# buck.net
KiCad netlist of a schematic drawn in EAGLE
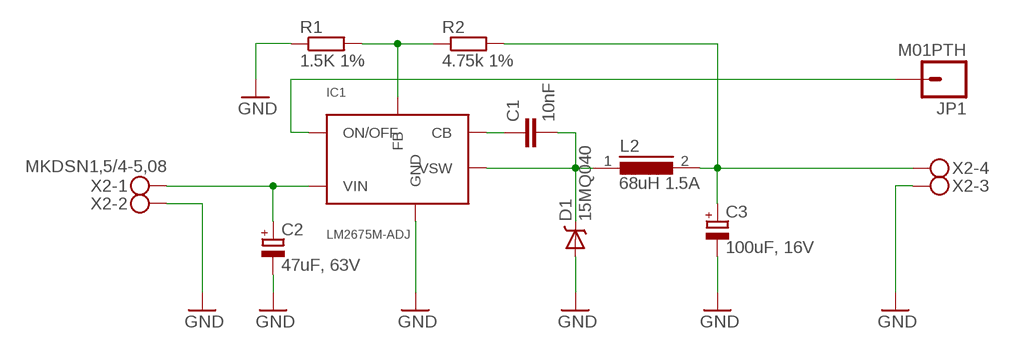
[diagram p0: schematic, sheet 1]

(export (version "E")
  (design (tool "Eeschema 10.0.6"))
  (components
    (comp (ref "C1")
      (value "10nF")
      (footprint "eagle-import:C0805")
      (libsource (lib "eagle-import") (part "C-EUC0805"))
    )
    (comp (ref "C2")
      (value "47uF, 63V")
      (footprint "eagle-import:PANASONIC_F")
      (libsource (lib "eagle-import") (part "CPOL-EUF"))
    )
    (comp (ref "C3")
      (value "100uF, 16V")
      (footprint "eagle-import:PANASONIC_D")
      (libsource (lib "eagle-import") (part "CPOL-EUD"))
    )
    (comp (ref "D1")
      (value "15MQ040")
      (footprint "eagle-import:SMA-DIODE")
      (libsource (lib "eagle-import") (part "DIODE-SCHOTTKY-MBRA140"))
    )
    (comp (ref "IC1")
      (value "LM2675M-ADJ")
      (footprint "eagle-import:SO-08")
      (libsource (lib "eagle-import") (part "LM2674"))
    )
    (comp (ref "JP1")
      (value "M01PTH")
      (footprint "eagle-import:1X01")
      (libsource (lib "eagle-import") (part "M01PTH"))
    )
    (comp (ref "L2")
      (value "68uH 1.5A")
      (footprint "eagle-import:DR125")
      (libsource (lib "eagle-import") (part "DR125"))
    )
    (comp (ref "R1")
      (value "1.5K 1%")
      (footprint "eagle-import:R0805W")
      (libsource (lib "eagle-import") (part "R-EU_R0805W"))
    )
    (comp (ref "R2")
      (value "4.75k 1%")
      (footprint "eagle-import:R0805W")
      (libsource (lib "eagle-import") (part "R-EU_R0805W"))
    )
    (comp (ref "X2")
      (value "MKDSN1,5/4-5,08")
      (footprint "eagle-import:MKDSN1,5_4-5,08")
      (fields (field (name "MPN") "SMKDSN1,5/4-5,08"))
      (libsource (lib "eagle-import") (part "MKDSN1,5/4-5,08"))
    )
  )
  (nets
    (net (code "1") (name "GND") (class "Default")
      (node (ref "C2") (pin "-") (pinfunction "-_-") (pintype "passive"))
      (node (ref "C3") (pin "-") (pinfunction "-_-") (pintype "passive"))
      (node (ref "D1") (pin "A") (pinfunction "A_A") (pintype "passive"))
      (node (ref "IC1") (pin "6") (pinfunction "GND_6") (pintype "bidirectional"))
      (node (ref "R1") (pin "1") (pinfunction "1_1") (pintype "passive"))
      (node (ref "X2") (pin "2") (pinfunction "KL_2") (pintype "passive"))
      (node (ref "X2") (pin "3") (pinfunction "KL_3") (pintype "passive"))
    )
    (net (code "2") (name "Net-(IC1-CB)") (class "Default")
      (node (ref "C1") (pin "1") (pinfunction "1_1") (pintype "passive"))
      (node (ref "IC1") (pin "1") (pinfunction "CB_1") (pintype "bidirectional"))
    )
    (net (code "3") (name "Net-(IC1-FB)") (class "Default")
      (node (ref "IC1") (pin "4") (pinfunction "FB_4") (pintype "bidirectional"))
      (node (ref "R1") (pin "2") (pinfunction "2_2") (pintype "passive"))
      (node (ref "R2") (pin "1") (pinfunction "1_1") (pintype "passive"))
    )
    (net (code "4") (name "Net-(IC1-ON{slash}OFF)") (class "Default")
      (node (ref "IC1") (pin "5") (pinfunction "ON/OFF_5") (pintype "bidirectional"))
      (node (ref "JP1") (pin "1") (pinfunction "1_1") (pintype "passive"))
    )
    (net (code "5") (name "Net-(IC1-VIN)") (class "Default")
      (node (ref "C2") (pin "+") (pinfunction "+_+") (pintype "passive"))
      (node (ref "IC1") (pin "7") (pinfunction "VIN_7") (pintype "bidirectional"))
      (node (ref "X2") (pin "1") (pinfunction "KL_1") (pintype "passive"))
    )
    (net (code "6") (name "Net-(IC1-VSW)") (class "Default")
      (node (ref "C1") (pin "2") (pinfunction "2_2") (pintype "passive"))
      (node (ref "D1") (pin "C") (pinfunction "C_C") (pintype "passive"))
      (node (ref "IC1") (pin "8") (pinfunction "VSW_8") (pintype "bidirectional"))
      (node (ref "L2") (pin "1") (pinfunction "1_1") (pintype "passive"))
    )
    (net (code "7") (name "Net-(X2D-KL)") (class "Default")
      (node (ref "C3") (pin "+") (pinfunction "+_+") (pintype "passive"))
      (node (ref "L2") (pin "2") (pinfunction "2_2") (pintype "passive"))
      (node (ref "R2") (pin "2") (pinfunction "2_2") (pintype "passive"))
      (node (ref "X2") (pin "4") (pinfunction "KL_4") (pintype "passive"))
    )
  )
)
